# STM32_MCU.net
KiCad netlist of a schematic drawn in Altium Designer
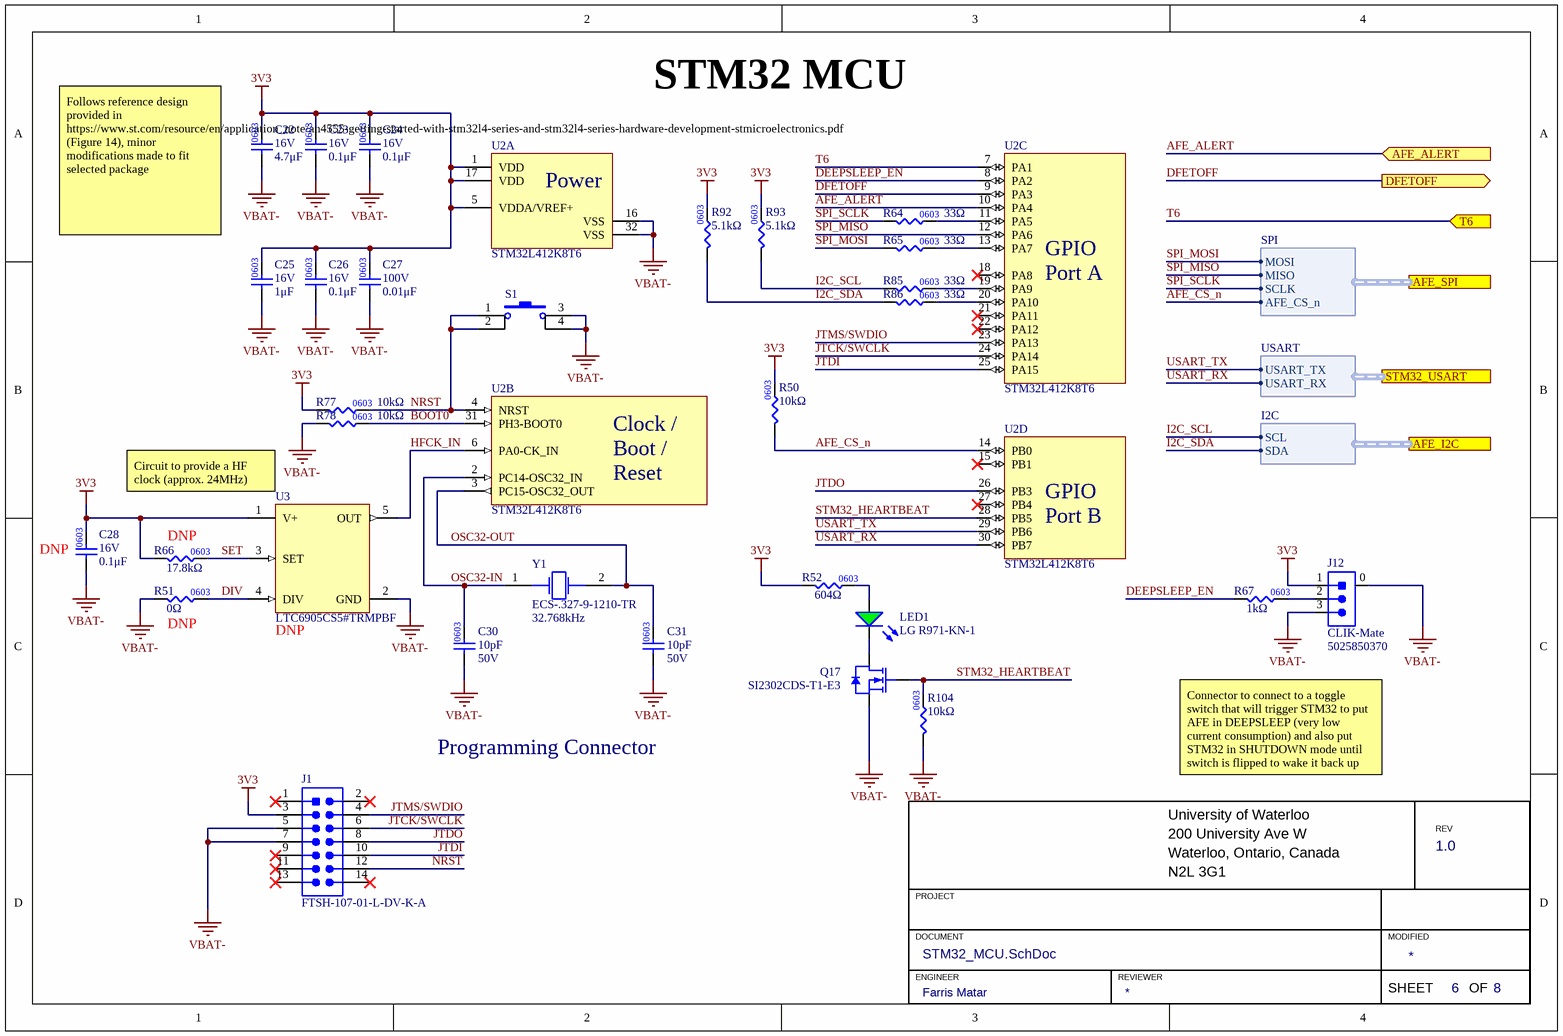
[diagram p0: STM32_MCU.SchDoc]

(export (version "E")
  (design (tool "Eeschema 10.0.6"))
  (components
    (comp (ref "C22")
      (value "4.7μF")
      (footprint "CAP0603")
      (description "CAP CER 4.7UF 16V X6S 0603")
      (fields (field (name "VOLTAGE RATING") "16V") (field (name "Comment") "CAP_4.7uF_16V_0603"))
      (libsource (lib "Personal_Schematic_Library_2022") (part "CAP_4.7uF_16V_0603"))
    )
    (comp (ref "C23")
      (value "0.1μF")
      (footprint "CAP0603")
      (description "CAP CER 0.1UF 16V X7R 0603")
      (fields (field (name "VOLTAGE RATING") "16V") (field (name "Comment") "CAP_0.1uF_16V_0603"))
      (libsource (lib "Personal_Schematic_Library_2022") (part "CAP_0.1uF_16V_0603"))
    )
    (comp (ref "C24")
      (value "0.1μF")
      (footprint "CAP0603")
      (description "CAP CER 0.1UF 16V X7R 0603")
      (fields (field (name "VOLTAGE RATING") "16V") (field (name "Comment") "CAP_0.1uF_16V_0603"))
      (libsource (lib "Personal_Schematic_Library_2022") (part "CAP_0.1uF_16V_0603"))
    )
    (comp (ref "C25")
      (value "1μF")
      (footprint "CAP0603")
      (description "CAP CER 1UF 16V X7R 0603")
      (fields (field (name "VOLTAGE RATING") "16V") (field (name "Comment") "CAP_1uF_16V_0603"))
      (libsource (lib "Personal_Schematic_Library_2022") (part "CAP_1uF_16V_0603"))
    )
    (comp (ref "C26")
      (value "0.1μF")
      (footprint "CAP0603")
      (description "CAP CER 0.1UF 16V X7R 0603")
      (fields (field (name "VOLTAGE RATING") "16V") (field (name "Comment") "CAP_0.1uF_16V_0603"))
      (libsource (lib "Personal_Schematic_Library_2022") (part "CAP_0.1uF_16V_0603"))
    )
    (comp (ref "C27")
      (value "0.01μF")
      (footprint "CAP0603")
      (description "CAP CER 0.01uF 100V X7R 0603")
      (fields (field (name "VOLTAGE RATING") "100V") (field (name "Comment") "CAP_0.01uF_100V_0603"))
      (libsource (lib "Personal_Schematic_Library_2022") (part "CAP_0.01uF_100V_0603"))
    )
    (comp (ref "C28")
      (value "0.1μF")
      (footprint "CAP0603")
      (description "CAP CER 0.1UF 16V X7R 0603")
      (fields (field (name "VOLTAGE RATING") "16V") (field (name "Comment") "CAP_0.1uF_16V_0603"))
      (libsource (lib "Personal_Schematic_Library_2022") (part "CAP_0.1uF_16V_0603"))
    )
    (comp (ref "C30")
      (value "10pF")
      (footprint "CAP0603")
      (description "CAP CER 10PF 50V X7R 0603")
      (fields (field (name "VOLTAGE RATING") "50V") (field (name "Comment") "CAP_10pF_50V_0603"))
      (libsource (lib "Personal_Schematic_Library_2022") (part "CAP_10pF_50V_0603"))
    )
    (comp (ref "C31")
      (value "10pF")
      (footprint "CAP0603")
      (description "CAP CER 10PF 50V X7R 0603")
      (fields (field (name "VOLTAGE RATING") "50V") (field (name "Comment") "CAP_10pF_50V_0603"))
      (libsource (lib "Personal_Schematic_Library_2022") (part "CAP_10pF_50V_0603"))
    )
    (comp (ref "J1")
      (value "CON_SAMTEC-FTSH_7x2_SMD")
      (footprint "SAMTEC-FTSH 7x2 SMD")
      (description "CONN HEADER SMD 14POS 1.27MM")
      (fields (field (name "MANUFACTURER PART NUMBER 1") "FTSH-107-01-L-DV-K-A"))
      (libsource (lib "Personal_Schematic_Library_2022") (part "CON_SAMTEC-FTSH_7x2_SMD"))
    )
    (comp (ref "J12")
      (value "CON_3M_SM_RA")
      (footprint "MOLEX-5025850370")
      (description "CONN RCPT 3POS 0.059 TIN SMD R/A")
      (fields (field (name "FAMILY") "CLIK-Mate") (field (name "MANUFACTURER PART NUMBER 1") "5025850370"))
      (libsource (lib "Personal_Schematic_Library_2022") (part "CON_3M_SM_RA"))
    )
    (comp (ref "LED1")
      (value "LED_GREEN")
      (footprint "LED_0805_GREEN")
      (description "LED GREEN DIFFUSED 0805 SMD")
      (fields (field (name "MANUFACTURER PART NUMBER 1") "LG R971-KN-1"))
      (libsource (lib "Personal_Schematic_Library_2022") (part "LED_GREEN"))
    )
    (comp (ref "Q17")
      (value "NMOS_20V_6A")
      (footprint "SOT23-3")
      (description "MOSFET N-CH 20V 2.6A SOT23-3")
      (fields (field (name "MANUFACTURER PART NUMBER 1") "SI2302CDS-T1-E3"))
      (libsource (lib "Personal_Schematic_Library_2022") (part "NMOS_20V_2.6A"))
    )
    (comp (ref "R50")
      (value "10kΩ")
      (footprint "RES0603")
      (description "RES 10K OHM 1% 1/8W 0603")
      (fields (field (name "Comment") "RES_10kΩ_0603_1%"))
      (libsource (lib "Personal_Schematic_Library_2022") (part "RES_10kΩ_0603_1%"))
    )
    (comp (ref "R51")
      (value "0Ω")
      (footprint "RES0603")
      (description "RES 0 OHM JUMPER 1/10W 0603")
      (fields (field (name "Comment") "RES_0Ω_0603"))
      (libsource (lib "Personal_Schematic_Library_2022") (part "RES_0Ω_0603"))
    )
    (comp (ref "R52")
      (value "604Ω")
      (footprint "RES0603")
      (description "RES 604 OHM 1% 1/10W 0603")
      (fields (field (name "Comment") "RES_604Ω_0603_1%"))
      (libsource (lib "Personal_Schematic_Library_2022") (part "RES_604Ω_0603_1%"))
    )
    (comp (ref "R64")
      (value "33Ω")
      (footprint "RES0603")
      (description "RES 33 OHM 1% 1/10W 0603")
      (fields (field (name "Comment") "RES_33Ω_0603_1%"))
      (libsource (lib "Personal_Schematic_Library_2022") (part "RES_33Ω_0603_1%"))
    )
    (comp (ref "R65")
      (value "33Ω")
      (footprint "RES0603")
      (description "RES 33 OHM 1% 1/10W 0603")
      (fields (field (name "Comment") "RES_33Ω_0603_1%"))
      (libsource (lib "Personal_Schematic_Library_2022") (part "RES_33Ω_0603_1%"))
    )
    (comp (ref "R66")
      (value "17.8kΩ")
      (footprint "RES0603")
      (description "RES 17.8K OHM 1% 1/10W 0603")
      (fields (field (name "Comment") "RES_17.8kΩ_0603_1%"))
      (libsource (lib "Personal_Schematic_Library_2022") (part "RES_17.8kΩ_0603_1%"))
    )
    (comp (ref "R67")
      (value "1kΩ")
      (footprint "RES0603")
      (description "RES 1K OHM 1% 1/8W 0603")
      (fields (field (name "Comment") "RES_1kΩ_0603_1%"))
      (libsource (lib "Personal_Schematic_Library_2022") (part "RES_1kΩ_0603_1%"))
    )
    (comp (ref "R77")
      (value "10kΩ")
      (footprint "RES0603")
      (description "RES 10K OHM 1% 1/8W 0603")
      (fields (field (name "Comment") "RES_10kΩ_0603_1%"))
      (libsource (lib "Personal_Schematic_Library_2022") (part "RES_10kΩ_0603_1%"))
    )
    (comp (ref "R78")
      (value "10kΩ")
      (footprint "RES0603")
      (description "RES 10K OHM 1% 1/8W 0603")
      (fields (field (name "Comment") "RES_10kΩ_0603_1%"))
      (libsource (lib "Personal_Schematic_Library_2022") (part "RES_10kΩ_0603_1%"))
    )
    (comp (ref "R85")
      (value "33Ω")
      (footprint "RES0603")
      (description "RES 33 OHM 1% 1/10W 0603")
      (fields (field (name "Comment") "RES_33Ω_0603_1%"))
      (libsource (lib "Personal_Schematic_Library_2022") (part "RES_33Ω_0603_1%"))
    )
    (comp (ref "R86")
      (value "33Ω")
      (footprint "RES0603")
      (description "RES 33 OHM 1% 1/10W 0603")
      (fields (field (name "Comment") "RES_33Ω_0603_1%"))
      (libsource (lib "Personal_Schematic_Library_2022") (part "RES_33Ω_0603_1%"))
    )
    (comp (ref "R92")
      (value "5.1kΩ")
      (footprint "RES0603")
      (description "RES 5.1K OHM 1% 1/10W 0603")
      (fields (field (name "Comment") "RES_5.1kΩ_0603_1%"))
      (libsource (lib "Personal_Schematic_Library_2022") (part "RES_5.1kΩ_0603_1%"))
    )
    (comp (ref "R93")
      (value "5.1kΩ")
      (footprint "RES0603")
      (description "RES 5.1K OHM 1% 1/10W 0603")
      (fields (field (name "Comment") "RES_5.1kΩ_0603_1%"))
      (libsource (lib "Personal_Schematic_Library_2022") (part "RES_5.1kΩ_0603_1%"))
    )
    (comp (ref "R104")
      (value "10kΩ")
      (footprint "RES0603")
      (description "RES 10K OHM 1% 1/8W 0603")
      (fields (field (name "Comment") "RES_10kΩ_0603_1%"))
      (libsource (lib "Personal_Schematic_Library_2022") (part "RES_10kΩ_0603_1%"))
    )
    (comp (ref "S1")
      (value "SW_SPST_NO_4.5x4.5")
      (footprint "SPST_PUSHBUTTON_TL3305AF260QG")
      (description "SWITCH TACTILE SPST-NO 50MA 12V")
      (libsource (lib "Personal_Schematic_Library_2022") (part "SW_SPST_NO_4.5x4.5"))
    )
    (comp (ref "U2")
      (value "STM32L412K8T6")
      (footprint "STM-LQFP32")
      (description "IC MCU 32BIT 64KB FLASH 32LQFP")
      (libsource (lib "Personal_Schematic_Library_2022") (part "STM32L412K8T6"))
    )
    (comp (ref "U3")
      (value "LTC6905CS5#TRMPBF")
      (footprint "SOT23-5")
      (description "IC OSC SILICON PROG TSOT23-5")
      (libsource (lib "Personal_Schematic_Library_2022") (part "IC_OSC_LTC6905"))
    )
    (comp (ref "Y1")
      (value "CRYSTAL_32.768KHZ")
      (footprint "OSC_ECS-327TR-2")
      (description "CRYSTAL 32.7680KHZ 9PF SMD")
      (fields
        (field (name "FREQUENCY") "32.768kHz")
        (field (name "MANUFACTURER PART NUMBER 1") "ECS-.327-9-1210-TR")
      )
      (libsource (lib "Personal_Schematic_Library_2022") (part "CRYSTAL_32.768KHZ"))
    )
  )
  (nets
    (net (code "4") (name "/AFE_ALERT") (class "Default")
      (node (ref "U2") (pin "10") (pinfunction "PA4_10") (pintype "bidirectional"))
    )
    (net (code "5") (name "/AFE_CS_n") (class "Default")
      (node (ref "R50") (pin "1") (pinfunction "1_1") (pintype "passive"))
      (node (ref "U2") (pin "14") (pinfunction "PB0_14") (pintype "bidirectional"))
    )
    (net (code "6") (name "/BOOT0") (class "Default")
      (node (ref "R78") (pin "2") (pinfunction "2_2") (pintype "passive"))
      (node (ref "U2") (pin "31") (pinfunction "PH3-BOOT0_31") (pintype "input"))
    )
    (net (code "7") (name "/DEEPSLEEP_EN") (class "Default")
      (node (ref "R67") (pin "1") (pinfunction "1_1") (pintype "passive"))
      (node (ref "U2") (pin "8") (pinfunction "PA2_8") (pintype "bidirectional"))
    )
    (net (code "8") (name "/DFETOFF") (class "Default")
      (node (ref "U2") (pin "9") (pinfunction "PA3_9") (pintype "bidirectional"))
    )
    (net (code "9") (name "/DIV") (class "Default")
      (node (ref "R51") (pin "2") (pinfunction "2_2") (pintype "passive"))
      (node (ref "U3") (pin "4") (pinfunction "DIV_4") (pintype "input"))
    )
    (net (code "10") (name "/HFCK_IN") (class "Default")
      (node (ref "U2") (pin "6") (pinfunction "PA0-CK_IN_6") (pintype "input"))
      (node (ref "U3") (pin "5") (pinfunction "OUT_5") (pintype "output"))
    )
    (net (code "11") (name "/I2C_SCL") (class "Default")
      (node (ref "R85") (pin "1") (pinfunction "1_1") (pintype "passive"))
      (node (ref "R93") (pin "1") (pinfunction "1_1") (pintype "passive"))
    )
    (net (code "12") (name "/I2C_SDA") (class "Default")
      (node (ref "R86") (pin "1") (pinfunction "1_1") (pintype "passive"))
      (node (ref "R92") (pin "1") (pinfunction "1_1") (pintype "passive"))
    )
    (net (code "13") (name "/JTCK{slash}SWCLK") (class "Default")
      (node (ref "J1") (pin "6") (pinfunction "6_6") (pintype "passive"))
      (node (ref "U2") (pin "24") (pinfunction "PA14_24") (pintype "bidirectional"))
    )
    (net (code "14") (name "/JTDI") (class "Default")
      (node (ref "J1") (pin "10") (pinfunction "10_10") (pintype "passive"))
      (node (ref "U2") (pin "25") (pinfunction "PA15_25") (pintype "bidirectional"))
    )
    (net (code "15") (name "/JTDO") (class "Default")
      (node (ref "J1") (pin "8") (pinfunction "8_8") (pintype "passive"))
      (node (ref "U2") (pin "26") (pinfunction "PB3_26") (pintype "bidirectional"))
    )
    (net (code "16") (name "/JTMS{slash}SWDIO") (class "Default")
      (node (ref "J1") (pin "4") (pinfunction "4_4") (pintype "passive"))
      (node (ref "U2") (pin "23") (pinfunction "PA13_23") (pintype "bidirectional"))
    )
    (net (code "17") (name "/NRST") (class "Default")
      (node (ref "J1") (pin "12") (pinfunction "12_12") (pintype "passive"))
      (node (ref "R77") (pin "2") (pinfunction "2_2") (pintype "passive"))
      (node (ref "S1") (pin "1") (pinfunction "1_1") (pintype "passive"))
      (node (ref "S1") (pin "2") (pinfunction "2_2") (pintype "passive"))
      (node (ref "U2") (pin "4") (pinfunction "NRST_4") (pintype "input"))
    )
    (net (code "18") (name "/OSC32-IN") (class "Default")
      (node (ref "C30") (pin "2") (pinfunction "2_2") (pintype "passive"))
      (node (ref "U2") (pin "2") (pinfunction "PC14-OSC32_IN_2") (pintype "input"))
      (node (ref "Y1") (pin "1") (pinfunction "1_1") (pintype "passive"))
    )
    (net (code "19") (name "/OSC32-OUT") (class "Default")
      (node (ref "C31") (pin "2") (pinfunction "2_2") (pintype "passive"))
      (node (ref "U2") (pin "3") (pinfunction "PC15-OSC32_OUT_3") (pintype "output"))
      (node (ref "Y1") (pin "2") (pinfunction "2_2") (pintype "passive"))
    )
    (net (code "20") (name "/SET") (class "Default")
      (node (ref "R66") (pin "2") (pinfunction "2_2") (pintype "passive"))
      (node (ref "U3") (pin "3") (pinfunction "SET_3") (pintype "input"))
    )
    (net (code "21") (name "/SPI_MISO") (class "Default")
      (node (ref "U2") (pin "12") (pinfunction "PA6_12") (pintype "bidirectional"))
    )
    (net (code "22") (name "/SPI_MOSI") (class "Default")
      (node (ref "R65") (pin "1") (pinfunction "1_1") (pintype "passive"))
    )
    (net (code "23") (name "/SPI_SCLK") (class "Default")
      (node (ref "R64") (pin "1") (pinfunction "1_1") (pintype "passive"))
    )
    (net (code "24") (name "/STM32_HEARTBEAT") (class "Default")
      (node (ref "Q17") (pin "1") (pinfunction "GATE_1") (pintype "passive"))
      (node (ref "R104") (pin "2") (pinfunction "2_2") (pintype "passive"))
      (node (ref "U2") (pin "28") (pinfunction "PB5_28") (pintype "bidirectional"))
    )
    (net (code "25") (name "/T6") (class "Default")
      (node (ref "U2") (pin "7") (pinfunction "PA1_7") (pintype "bidirectional"))
    )
    (net (code "26") (name "/USART_RX") (class "Default")
      (node (ref "U2") (pin "30") (pinfunction "PB7_30") (pintype "bidirectional"))
    )
    (net (code "27") (name "/USART_TX") (class "Default")
      (node (ref "U2") (pin "29") (pinfunction "PB6_29") (pintype "bidirectional"))
    )
    (net (code "31") (name "3V3") (class "Default")
      (node (ref "C22") (pin "2") (pinfunction "2_2") (pintype "passive"))
      (node (ref "C23") (pin "2") (pinfunction "2_2") (pintype "passive"))
      (node (ref "C24") (pin "2") (pinfunction "2_2") (pintype "passive"))
      (node (ref "C25") (pin "2") (pinfunction "2_2") (pintype "passive"))
      (node (ref "C26") (pin "2") (pinfunction "2_2") (pintype "passive"))
      (node (ref "C27") (pin "2") (pinfunction "2_2") (pintype "passive"))
      (node (ref "C28") (pin "2") (pinfunction "2_2") (pintype "passive"))
      (node (ref "J1") (pin "3") (pinfunction "3_3") (pintype "passive"))
      (node (ref "J12") (pin "1") (pinfunction "1_1") (pintype "passive"))
      (node (ref "R50") (pin "2") (pinfunction "2_2") (pintype "passive"))
      (node (ref "R52") (pin "1") (pinfunction "1_1") (pintype "passive"))
      (node (ref "R66") (pin "1") (pinfunction "1_1") (pintype "passive"))
      (node (ref "R77") (pin "1") (pinfunction "1_1") (pintype "passive"))
      (node (ref "R92") (pin "2") (pinfunction "2_2") (pintype "passive"))
      (node (ref "R93") (pin "2") (pinfunction "2_2") (pintype "passive"))
      (node (ref "U2") (pin "1") (pinfunction "VDD_1") (pintype "power_in"))
      (node (ref "U2") (pin "17") (pinfunction "VDD_17") (pintype "power_in"))
      (node (ref "U2") (pin "5") (pinfunction "VDDA/VREF+_5") (pintype "power_in"))
      (node (ref "U3") (pin "1") (pinfunction "V+_1") (pintype "power_in"))
    )
    (net (code "32") (name "Net-(J12-Pad2)") (class "Default")
      (node (ref "J12") (pin "2") (pinfunction "2_2") (pintype "passive"))
      (node (ref "R67") (pin "2") (pinfunction "2_2") (pintype "passive"))
    )
    (net (code "33") (name "Net-(LED1-A)") (class "Default")
      (node (ref "LED1") (pin "1") (pinfunction "A_1") (pintype "passive"))
      (node (ref "R52") (pin "2") (pinfunction "2_2") (pintype "passive"))
    )
    (net (code "34") (name "Net-(LED1-K)") (class "Default")
      (node (ref "LED1") (pin "2") (pinfunction "K_2") (pintype "passive"))
      (node (ref "Q17") (pin "3") (pinfunction "DRAIN_3") (pintype "passive"))
    )
    (net (code "35") (name "Net-(U2C-PA5)") (class "Default")
      (node (ref "R64") (pin "2") (pinfunction "2_2") (pintype "passive"))
      (node (ref "U2") (pin "11") (pinfunction "PA5_11") (pintype "bidirectional"))
    )
    (net (code "36") (name "Net-(U2C-PA7)") (class "Default")
      (node (ref "R65") (pin "2") (pinfunction "2_2") (pintype "passive"))
      (node (ref "U2") (pin "13") (pinfunction "PA7_13") (pintype "bidirectional"))
    )
    (net (code "37") (name "Net-(U2C-PA9)") (class "Default")
      (node (ref "R85") (pin "2") (pinfunction "2_2") (pintype "passive"))
      (node (ref "U2") (pin "19") (pinfunction "PA9_19") (pintype "bidirectional"))
    )
    (net (code "38") (name "Net-(U2C-PA10)") (class "Default")
      (node (ref "R86") (pin "2") (pinfunction "2_2") (pintype "passive"))
      (node (ref "U2") (pin "20") (pinfunction "PA10_20") (pintype "bidirectional"))
    )
    (net (code "39") (name "VBAT-") (class "Default")
      (node (ref "C22") (pin "1") (pinfunction "1_1") (pintype "passive"))
      (node (ref "C23") (pin "1") (pinfunction "1_1") (pintype "passive"))
      (node (ref "C24") (pin "1") (pinfunction "1_1") (pintype "passive"))
      (node (ref "C25") (pin "1") (pinfunction "1_1") (pintype "passive"))
      (node (ref "C26") (pin "1") (pinfunction "1_1") (pintype "passive"))
      (node (ref "C27") (pin "1") (pinfunction "1_1") (pintype "passive"))
      (node (ref "C28") (pin "1") (pinfunction "1_1") (pintype "passive"))
      (node (ref "C30") (pin "1") (pinfunction "1_1") (pintype "passive"))
      (node (ref "C31") (pin "1") (pinfunction "1_1") (pintype "passive"))
      (node (ref "J1") (pin "5") (pinfunction "5_5") (pintype "passive"))
      (node (ref "J1") (pin "7") (pinfunction "7_7") (pintype "passive"))
      (node (ref "J12") (pin "0") (pinfunction "0_0") (pintype "passive"))
      (node (ref "J12") (pin "3") (pinfunction "3_3") (pintype "passive"))
      (node (ref "Q17") (pin "2") (pinfunction "SOURCE_2") (pintype "passive"))
      (node (ref "R104") (pin "1") (pinfunction "1_1") (pintype "passive"))
      (node (ref "R51") (pin "1") (pinfunction "1_1") (pintype "passive"))
      (node (ref "R78") (pin "1") (pinfunction "1_1") (pintype "passive"))
      (node (ref "S1") (pin "3") (pinfunction "3_3") (pintype "passive"))
      (node (ref "S1") (pin "4") (pinfunction "4_4") (pintype "passive"))
      (node (ref "U2") (pin "16") (pinfunction "VSS_16") (pintype "power_in"))
      (node (ref "U2") (pin "32") (pinfunction "VSS_32") (pintype "power_in"))
      (node (ref "U3") (pin "2") (pinfunction "GND_2") (pintype "power_in"))
    )
    (net (code "40") (name "unconnected-(J1-Pad1)") (class "Default")
      (node (ref "J1") (pin "1") (pinfunction "1_1") (pintype "passive+no_connect"))
    )
    (net (code "41") (name "unconnected-(J1-Pad2)") (class "Default")
      (node (ref "J1") (pin "2") (pinfunction "2_2") (pintype "passive+no_connect"))
    )
    (net (code "42") (name "unconnected-(J1-Pad9)") (class "Default")
      (node (ref "J1") (pin "9") (pinfunction "9_9") (pintype "passive+no_connect"))
    )
    (net (code "43") (name "unconnected-(J1-Pad11)") (class "Default")
      (node (ref "J1") (pin "11") (pinfunction "11_11") (pintype "passive+no_connect"))
    )
    (net (code "44") (name "unconnected-(J1-Pad13)") (class "Default")
      (node (ref "J1") (pin "13") (pinfunction "13_13") (pintype "passive+no_connect"))
    )
    (net (code "45") (name "unconnected-(J1-Pad14)") (class "Default")
      (node (ref "J1") (pin "14") (pinfunction "14_14") (pintype "passive+no_connect"))
    )
    (net (code "46") (name "unconnected-(U2C-PA8-Pad18)") (class "Default")
      (node (ref "U2") (pin "18") (pinfunction "PA8_18") (pintype "bidirectional+no_connect"))
    )
    (net (code "47") (name "unconnected-(U2C-PA11-Pad21)") (class "Default")
      (node (ref "U2") (pin "21") (pinfunction "PA11_21") (pintype "bidirectional+no_connect"))
    )
    (net (code "48") (name "unconnected-(U2C-PA12-Pad22)") (class "Default")
      (node (ref "U2") (pin "22") (pinfunction "PA12_22") (pintype "bidirectional+no_connect"))
    )
    (net (code "49") (name "unconnected-(U2D-PB1-Pad15)") (class "Default")
      (node (ref "U2") (pin "15") (pinfunction "PB1_15") (pintype "bidirectional+no_connect"))
    )
    (net (code "50") (name "unconnected-(U2D-PB4-Pad27)") (class "Default")
      (node (ref "U2") (pin "27") (pinfunction "PB4_27") (pintype "bidirectional+no_connect"))
    )
  )
)
